# USST_ARM.net
KiCad netlist of a schematic drawn in Altium Designer
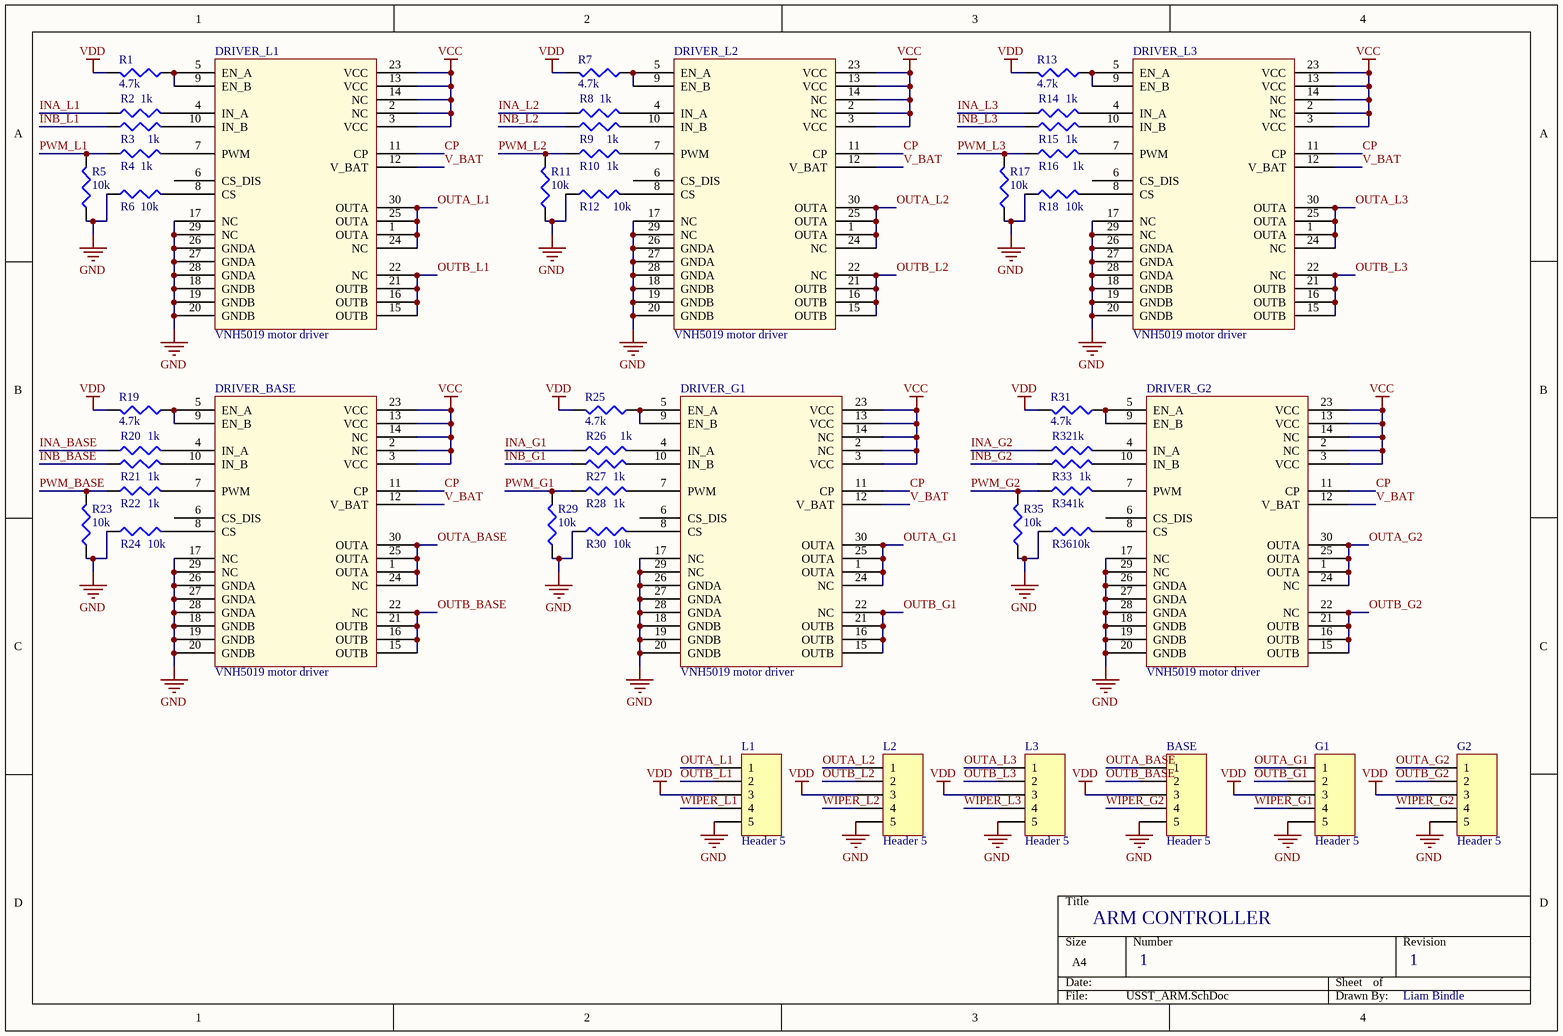
[diagram p0: USST_ARM.SchDoc]

(export (version "E")
  (design (tool "Eeschema 10.0.6"))
  (components
    (comp (ref "BASE")
      (value "Header 5")
      (footprint "HDR1X5")
      (description "Header, 5-Pin")
      (fields (field (name "PUBLISHER") "Altium Limited"))
      (libsource (lib "Miscellaneous Connectors") (part "Header 5"))
    )
    (comp (ref "DRIVER_BASE")
      (value "VNH5019 motor driver")
      (footprint "VNH5019_USST")
      (description "Motor driver")
      (libsource (lib "VNH5019_USST") (part "Component_1"))
    )
    (comp (ref "DRIVER_G1")
      (value "VNH5019 motor driver")
      (footprint "VNH5019_USST")
      (description "Motor driver")
      (libsource (lib "VNH5019_USST") (part "Component_1"))
    )
    (comp (ref "DRIVER_G2")
      (value "VNH5019 motor driver")
      (footprint "VNH5019_USST")
      (description "Motor driver")
      (libsource (lib "VNH5019_USST") (part "Component_1"))
    )
    (comp (ref "DRIVER_L1")
      (value "VNH5019 motor driver")
      (footprint "VNH5019_USST")
      (description "Motor driver")
      (libsource (lib "VNH5019_USST") (part "Component_1"))
    )
    (comp (ref "DRIVER_L2")
      (value "VNH5019 motor driver")
      (footprint "VNH5019_USST")
      (description "Motor driver")
      (libsource (lib "VNH5019_USST") (part "Component_1"))
    )
    (comp (ref "DRIVER_L3")
      (value "VNH5019 motor driver")
      (footprint "VNH5019_USST")
      (description "Motor driver")
      (libsource (lib "VNH5019_USST") (part "Component_1"))
    )
    (comp (ref "G1")
      (value "Header 5")
      (footprint "HDR1X5")
      (description "Header, 5-Pin")
      (fields (field (name "PUBLISHER") "Altium Limited"))
      (libsource (lib "Miscellaneous Connectors") (part "Header 5"))
    )
    (comp (ref "G2")
      (value "Header 5")
      (footprint "HDR1X5")
      (description "Header, 5-Pin")
      (fields (field (name "PUBLISHER") "Altium Limited"))
      (libsource (lib "Miscellaneous Connectors") (part "Header 5"))
    )
    (comp (ref "L1")
      (value "Header 5")
      (footprint "HDR1X5")
      (description "Header, 5-Pin")
      (fields (field (name "PUBLISHER") "Altium Limited"))
      (libsource (lib "Miscellaneous Connectors") (part "Header 5"))
    )
    (comp (ref "L2")
      (value "Header 5")
      (footprint "HDR1X5")
      (description "Header, 5-Pin")
      (fields (field (name "PUBLISHER") "Altium Limited"))
      (libsource (lib "Miscellaneous Connectors") (part "Header 5"))
    )
    (comp (ref "L3")
      (value "Header 5")
      (footprint "HDR1X5")
      (description "Header, 5-Pin")
      (fields (field (name "PUBLISHER") "Altium Limited"))
      (libsource (lib "Miscellaneous Connectors") (part "Header 5"))
    )
    (comp (ref "R1")
      (value "4.7k")
      (footprint "J1-0603")
      (description "Resistor")
      (fields (field (name "Comment") "Res3") (field (name "PUBLISHER") "Altium Limited"))
      (libsource (lib "Miscellaneous Devices") (part "Res3"))
    )
    (comp (ref "R2")
      (value "1k")
      (footprint "J1-0603")
      (description "Resistor")
      (fields (field (name "Comment") "Res3") (field (name "PUBLISHER") "Altium Limited"))
      (libsource (lib "Miscellaneous Devices") (part "Res3"))
    )
    (comp (ref "R3")
      (value "1k")
      (footprint "J1-0603")
      (description "Resistor")
      (fields (field (name "Comment") "Res3") (field (name "PUBLISHER") "Altium Limited"))
      (libsource (lib "Miscellaneous Devices") (part "Res3"))
    )
    (comp (ref "R4")
      (value "1k")
      (footprint "J1-0603")
      (description "Resistor")
      (fields (field (name "Comment") "Res3") (field (name "PUBLISHER") "Altium Limited"))
      (libsource (lib "Miscellaneous Devices") (part "Res3"))
    )
    (comp (ref "R5")
      (value "10k")
      (footprint "J1-0603")
      (description "Resistor")
      (fields (field (name "Comment") "Res3") (field (name "PUBLISHER") "Altium Limited"))
      (libsource (lib "Miscellaneous Devices") (part "Res3"))
    )
    (comp (ref "R6")
      (value "10k")
      (footprint "J1-0603")
      (description "Resistor")
      (fields (field (name "Comment") "Res3") (field (name "PUBLISHER") "Altium Limited"))
      (libsource (lib "Miscellaneous Devices") (part "Res3"))
    )
    (comp (ref "R7")
      (value "4.7k")
      (footprint "J1-0603")
      (description "Resistor")
      (fields (field (name "Comment") "Res3") (field (name "PUBLISHER") "Altium Limited"))
      (libsource (lib "Miscellaneous Devices") (part "Res3"))
    )
    (comp (ref "R8")
      (value "1k")
      (footprint "J1-0603")
      (description "Resistor")
      (fields (field (name "Comment") "Res3") (field (name "PUBLISHER") "Altium Limited"))
      (libsource (lib "Miscellaneous Devices") (part "Res3"))
    )
    (comp (ref "R9")
      (value "1k")
      (footprint "J1-0603")
      (description "Resistor")
      (fields (field (name "Comment") "Res3") (field (name "PUBLISHER") "Altium Limited"))
      (libsource (lib "Miscellaneous Devices") (part "Res3"))
    )
    (comp (ref "R10")
      (value "1k")
      (footprint "J1-0603")
      (description "Resistor")
      (fields (field (name "Comment") "Res3") (field (name "PUBLISHER") "Altium Limited"))
      (libsource (lib "Miscellaneous Devices") (part "Res3"))
    )
    (comp (ref "R11")
      (value "10k")
      (footprint "J1-0603")
      (description "Resistor")
      (fields (field (name "Comment") "Res3") (field (name "PUBLISHER") "Altium Limited"))
      (libsource (lib "Miscellaneous Devices") (part "Res3"))
    )
    (comp (ref "R12")
      (value "10k")
      (footprint "J1-0603")
      (description "Resistor")
      (fields (field (name "Comment") "Res3") (field (name "PUBLISHER") "Altium Limited"))
      (libsource (lib "Miscellaneous Devices") (part "Res3"))
    )
    (comp (ref "R13")
      (value "4.7k")
      (footprint "J1-0603")
      (description "Resistor")
      (fields (field (name "Comment") "Res3") (field (name "PUBLISHER") "Altium Limited"))
      (libsource (lib "Miscellaneous Devices") (part "Res3"))
    )
    (comp (ref "R14")
      (value "1k")
      (footprint "J1-0603")
      (description "Resistor")
      (fields (field (name "Comment") "Res3") (field (name "PUBLISHER") "Altium Limited"))
      (libsource (lib "Miscellaneous Devices") (part "Res3"))
    )
    (comp (ref "R15")
      (value "1k")
      (footprint "J1-0603")
      (description "Resistor")
      (fields (field (name "Comment") "Res3") (field (name "PUBLISHER") "Altium Limited"))
      (libsource (lib "Miscellaneous Devices") (part "Res3"))
    )
    (comp (ref "R16")
      (value "1k")
      (footprint "J1-0603")
      (description "Resistor")
      (fields (field (name "Comment") "Res3") (field (name "PUBLISHER") "Altium Limited"))
      (libsource (lib "Miscellaneous Devices") (part "Res3"))
    )
    (comp (ref "R17")
      (value "10k")
      (footprint "J1-0603")
      (description "Resistor")
      (fields (field (name "Comment") "Res3") (field (name "PUBLISHER") "Altium Limited"))
      (libsource (lib "Miscellaneous Devices") (part "Res3"))
    )
    (comp (ref "R18")
      (value "10k")
      (footprint "J1-0603")
      (description "Resistor")
      (fields (field (name "Comment") "Res3") (field (name "PUBLISHER") "Altium Limited"))
      (libsource (lib "Miscellaneous Devices") (part "Res3"))
    )
    (comp (ref "R19")
      (value "4.7k")
      (footprint "J1-0603")
      (description "Resistor")
      (fields (field (name "Comment") "Res3") (field (name "PUBLISHER") "Altium Limited"))
      (libsource (lib "Miscellaneous Devices") (part "Res3"))
    )
    (comp (ref "R20")
      (value "1k")
      (footprint "J1-0603")
      (description "Resistor")
      (fields (field (name "Comment") "Res3") (field (name "PUBLISHER") "Altium Limited"))
      (libsource (lib "Miscellaneous Devices") (part "Res3"))
    )
    (comp (ref "R21")
      (value "1k")
      (footprint "J1-0603")
      (description "Resistor")
      (fields (field (name "Comment") "Res3") (field (name "PUBLISHER") "Altium Limited"))
      (libsource (lib "Miscellaneous Devices") (part "Res3"))
    )
    (comp (ref "R22")
      (value "1k")
      (footprint "J1-0603")
      (description "Resistor")
      (fields (field (name "Comment") "Res3") (field (name "PUBLISHER") "Altium Limited"))
      (libsource (lib "Miscellaneous Devices") (part "Res3"))
    )
    (comp (ref "R23")
      (value "10k")
      (footprint "J1-0603")
      (description "Resistor")
      (fields (field (name "Comment") "Res3") (field (name "PUBLISHER") "Altium Limited"))
      (libsource (lib "Miscellaneous Devices") (part "Res3"))
    )
    (comp (ref "R24")
      (value "10k")
      (footprint "J1-0603")
      (description "Resistor")
      (fields (field (name "Comment") "Res3") (field (name "PUBLISHER") "Altium Limited"))
      (libsource (lib "Miscellaneous Devices") (part "Res3"))
    )
    (comp (ref "R25")
      (value "4.7k")
      (footprint "J1-0603")
      (description "Resistor")
      (fields (field (name "Comment") "Res3") (field (name "PUBLISHER") "Altium Limited"))
      (libsource (lib "Miscellaneous Devices") (part "Res3"))
    )
    (comp (ref "R26")
      (value "1k")
      (footprint "J1-0603")
      (description "Resistor")
      (fields (field (name "Comment") "Res3") (field (name "PUBLISHER") "Altium Limited"))
      (libsource (lib "Miscellaneous Devices") (part "Res3"))
    )
    (comp (ref "R27")
      (value "1k")
      (footprint "J1-0603")
      (description "Resistor")
      (fields (field (name "Comment") "Res3") (field (name "PUBLISHER") "Altium Limited"))
      (libsource (lib "Miscellaneous Devices") (part "Res3"))
    )
    (comp (ref "R28")
      (value "1k")
      (footprint "J1-0603")
      (description "Resistor")
      (fields (field (name "Comment") "Res3") (field (name "PUBLISHER") "Altium Limited"))
      (libsource (lib "Miscellaneous Devices") (part "Res3"))
    )
    (comp (ref "R29")
      (value "10k")
      (footprint "J1-0603")
      (description "Resistor")
      (fields (field (name "Comment") "Res3") (field (name "PUBLISHER") "Altium Limited"))
      (libsource (lib "Miscellaneous Devices") (part "Res3"))
    )
    (comp (ref "R30")
      (value "10k")
      (footprint "J1-0603")
      (description "Resistor")
      (fields (field (name "Comment") "Res3") (field (name "PUBLISHER") "Altium Limited"))
      (libsource (lib "Miscellaneous Devices") (part "Res3"))
    )
    (comp (ref "R31")
      (value "4.7k")
      (footprint "J1-0603")
      (description "Resistor")
      (fields (field (name "Comment") "Res3") (field (name "PUBLISHER") "Altium Limited"))
      (libsource (lib "Miscellaneous Devices") (part "Res3"))
    )
    (comp (ref "R32")
      (value "1k")
      (footprint "J1-0603")
      (description "Resistor")
      (fields (field (name "Comment") "Res3") (field (name "PUBLISHER") "Altium Limited"))
      (libsource (lib "Miscellaneous Devices") (part "Res3"))
    )
    (comp (ref "R33")
      (value "1k")
      (footprint "J1-0603")
      (description "Resistor")
      (fields (field (name "Comment") "Res3") (field (name "PUBLISHER") "Altium Limited"))
      (libsource (lib "Miscellaneous Devices") (part "Res3"))
    )
    (comp (ref "R34")
      (value "1k")
      (footprint "J1-0603")
      (description "Resistor")
      (fields (field (name "Comment") "Res3") (field (name "PUBLISHER") "Altium Limited"))
      (libsource (lib "Miscellaneous Devices") (part "Res3"))
    )
    (comp (ref "R35")
      (value "10k")
      (footprint "J1-0603")
      (description "Resistor")
      (fields (field (name "Comment") "Res3") (field (name "PUBLISHER") "Altium Limited"))
      (libsource (lib "Miscellaneous Devices") (part "Res3"))
    )
    (comp (ref "R36")
      (value "10k")
      (footprint "J1-0603")
      (description "Resistor")
      (fields (field (name "Comment") "Res3") (field (name "PUBLISHER") "Altium Limited"))
      (libsource (lib "Miscellaneous Devices") (part "Res3"))
    )
  )
  (nets
    (net (code "1") (name "/CP") (class "Default")
      (node (ref "DRIVER_BASE") (pin "11") (pinfunction "CP_11") (pintype "passive"))
      (node (ref "DRIVER_G1") (pin "11") (pinfunction "CP_11") (pintype "passive"))
      (node (ref "DRIVER_G2") (pin "11") (pinfunction "CP_11") (pintype "passive"))
      (node (ref "DRIVER_L1") (pin "11") (pinfunction "CP_11") (pintype "passive"))
      (node (ref "DRIVER_L2") (pin "11") (pinfunction "CP_11") (pintype "passive"))
      (node (ref "DRIVER_L3") (pin "11") (pinfunction "CP_11") (pintype "passive"))
    )
    (net (code "2") (name "/INA_BASE") (class "Default")
      (node (ref "R20") (pin "1") (pinfunction "1_1") (pintype "passive"))
    )
    (net (code "3") (name "/INA_G1") (class "Default")
      (node (ref "R26") (pin "1") (pinfunction "1_1") (pintype "passive"))
    )
    (net (code "4") (name "/INA_G2") (class "Default")
      (node (ref "R32") (pin "1") (pinfunction "1_1") (pintype "passive"))
    )
    (net (code "5") (name "/INA_L1") (class "Default")
      (node (ref "R2") (pin "1") (pinfunction "1_1") (pintype "passive"))
    )
    (net (code "6") (name "/INA_L2") (class "Default")
      (node (ref "R8") (pin "1") (pinfunction "1_1") (pintype "passive"))
    )
    (net (code "7") (name "/INA_L3") (class "Default")
      (node (ref "R14") (pin "1") (pinfunction "1_1") (pintype "passive"))
    )
    (net (code "8") (name "/INB_BASE") (class "Default")
      (node (ref "R21") (pin "1") (pinfunction "1_1") (pintype "passive"))
    )
    (net (code "9") (name "/INB_G1") (class "Default")
      (node (ref "R27") (pin "1") (pinfunction "1_1") (pintype "passive"))
    )
    (net (code "10") (name "/INB_G2") (class "Default")
      (node (ref "R33") (pin "1") (pinfunction "1_1") (pintype "passive"))
    )
    (net (code "11") (name "/INB_L1") (class "Default")
      (node (ref "R3") (pin "1") (pinfunction "1_1") (pintype "passive"))
    )
    (net (code "12") (name "/INB_L2") (class "Default")
      (node (ref "R9") (pin "1") (pinfunction "1_1") (pintype "passive"))
    )
    (net (code "13") (name "/INB_L3") (class "Default")
      (node (ref "R15") (pin "1") (pinfunction "1_1") (pintype "passive"))
    )
    (net (code "14") (name "/OUTA_BASE") (class "Default")
      (node (ref "BASE") (pin "1") (pinfunction "1_1") (pintype "passive"))
      (node (ref "DRIVER_BASE") (pin "1") (pinfunction "OUTA_1") (pintype "passive"))
      (node (ref "DRIVER_BASE") (pin "24") (pinfunction "NC_24") (pintype "passive"))
      (node (ref "DRIVER_BASE") (pin "25") (pinfunction "OUTA_25") (pintype "passive"))
      (node (ref "DRIVER_BASE") (pin "30") (pinfunction "OUTA_30") (pintype "passive"))
    )
    (net (code "15") (name "/OUTA_G1") (class "Default")
      (node (ref "DRIVER_G1") (pin "1") (pinfunction "OUTA_1") (pintype "passive"))
      (node (ref "DRIVER_G1") (pin "24") (pinfunction "NC_24") (pintype "passive"))
      (node (ref "DRIVER_G1") (pin "25") (pinfunction "OUTA_25") (pintype "passive"))
      (node (ref "DRIVER_G1") (pin "30") (pinfunction "OUTA_30") (pintype "passive"))
      (node (ref "G1") (pin "1") (pinfunction "1_1") (pintype "passive"))
    )
    (net (code "16") (name "/OUTA_G2") (class "Default")
      (node (ref "DRIVER_G2") (pin "1") (pinfunction "OUTA_1") (pintype "passive"))
      (node (ref "DRIVER_G2") (pin "24") (pinfunction "NC_24") (pintype "passive"))
      (node (ref "DRIVER_G2") (pin "25") (pinfunction "OUTA_25") (pintype "passive"))
      (node (ref "DRIVER_G2") (pin "30") (pinfunction "OUTA_30") (pintype "passive"))
      (node (ref "G2") (pin "1") (pinfunction "1_1") (pintype "passive"))
    )
    (net (code "17") (name "/OUTA_L1") (class "Default")
      (node (ref "DRIVER_L1") (pin "1") (pinfunction "OUTA_1") (pintype "passive"))
      (node (ref "DRIVER_L1") (pin "24") (pinfunction "NC_24") (pintype "passive"))
      (node (ref "DRIVER_L1") (pin "25") (pinfunction "OUTA_25") (pintype "passive"))
      (node (ref "DRIVER_L1") (pin "30") (pinfunction "OUTA_30") (pintype "passive"))
      (node (ref "L1") (pin "1") (pinfunction "1_1") (pintype "passive"))
    )
    (net (code "18") (name "/OUTA_L2") (class "Default")
      (node (ref "DRIVER_L2") (pin "1") (pinfunction "OUTA_1") (pintype "passive"))
      (node (ref "DRIVER_L2") (pin "24") (pinfunction "NC_24") (pintype "passive"))
      (node (ref "DRIVER_L2") (pin "25") (pinfunction "OUTA_25") (pintype "passive"))
      (node (ref "DRIVER_L2") (pin "30") (pinfunction "OUTA_30") (pintype "passive"))
      (node (ref "L2") (pin "1") (pinfunction "1_1") (pintype "passive"))
    )
    (net (code "19") (name "/OUTA_L3") (class "Default")
      (node (ref "DRIVER_L3") (pin "1") (pinfunction "OUTA_1") (pintype "passive"))
      (node (ref "DRIVER_L3") (pin "24") (pinfunction "NC_24") (pintype "passive"))
      (node (ref "DRIVER_L3") (pin "25") (pinfunction "OUTA_25") (pintype "passive"))
      (node (ref "DRIVER_L3") (pin "30") (pinfunction "OUTA_30") (pintype "passive"))
      (node (ref "L3") (pin "1") (pinfunction "1_1") (pintype "passive"))
    )
    (net (code "20") (name "/OUTB_BASE") (class "Default")
      (node (ref "BASE") (pin "2") (pinfunction "2_2") (pintype "passive"))
      (node (ref "DRIVER_BASE") (pin "15") (pinfunction "OUTB_15") (pintype "passive"))
      (node (ref "DRIVER_BASE") (pin "16") (pinfunction "OUTB_16") (pintype "passive"))
      (node (ref "DRIVER_BASE") (pin "21") (pinfunction "OUTB_21") (pintype "passive"))
      (node (ref "DRIVER_BASE") (pin "22") (pinfunction "NC_22") (pintype "passive"))
    )
    (net (code "21") (name "/OUTB_G1") (class "Default")
      (node (ref "DRIVER_G1") (pin "15") (pinfunction "OUTB_15") (pintype "passive"))
      (node (ref "DRIVER_G1") (pin "16") (pinfunction "OUTB_16") (pintype "passive"))
      (node (ref "DRIVER_G1") (pin "21") (pinfunction "OUTB_21") (pintype "passive"))
      (node (ref "DRIVER_G1") (pin "22") (pinfunction "NC_22") (pintype "passive"))
      (node (ref "G1") (pin "2") (pinfunction "2_2") (pintype "passive"))
    )
    (net (code "22") (name "/OUTB_G2") (class "Default")
      (node (ref "DRIVER_G2") (pin "15") (pinfunction "OUTB_15") (pintype "passive"))
      (node (ref "DRIVER_G2") (pin "16") (pinfunction "OUTB_16") (pintype "passive"))
      (node (ref "DRIVER_G2") (pin "21") (pinfunction "OUTB_21") (pintype "passive"))
      (node (ref "DRIVER_G2") (pin "22") (pinfunction "NC_22") (pintype "passive"))
      (node (ref "G2") (pin "2") (pinfunction "2_2") (pintype "passive"))
    )
    (net (code "23") (name "/OUTB_L1") (class "Default")
      (node (ref "DRIVER_L1") (pin "15") (pinfunction "OUTB_15") (pintype "passive"))
      (node (ref "DRIVER_L1") (pin "16") (pinfunction "OUTB_16") (pintype "passive"))
      (node (ref "DRIVER_L1") (pin "21") (pinfunction "OUTB_21") (pintype "passive"))
      (node (ref "DRIVER_L1") (pin "22") (pinfunction "NC_22") (pintype "passive"))
      (node (ref "L1") (pin "2") (pinfunction "2_2") (pintype "passive"))
    )
    (net (code "24") (name "/OUTB_L2") (class "Default")
      (node (ref "DRIVER_L2") (pin "15") (pinfunction "OUTB_15") (pintype "passive"))
      (node (ref "DRIVER_L2") (pin "16") (pinfunction "OUTB_16") (pintype "passive"))
      (node (ref "DRIVER_L2") (pin "21") (pinfunction "OUTB_21") (pintype "passive"))
      (node (ref "DRIVER_L2") (pin "22") (pinfunction "NC_22") (pintype "passive"))
      (node (ref "L2") (pin "2") (pinfunction "2_2") (pintype "passive"))
    )
    (net (code "25") (name "/OUTB_L3") (class "Default")
      (node (ref "DRIVER_L3") (pin "15") (pinfunction "OUTB_15") (pintype "passive"))
      (node (ref "DRIVER_L3") (pin "16") (pinfunction "OUTB_16") (pintype "passive"))
      (node (ref "DRIVER_L3") (pin "21") (pinfunction "OUTB_21") (pintype "passive"))
      (node (ref "DRIVER_L3") (pin "22") (pinfunction "NC_22") (pintype "passive"))
      (node (ref "L3") (pin "2") (pinfunction "2_2") (pintype "passive"))
    )
    (net (code "26") (name "/PWM_BASE") (class "Default")
      (node (ref "R22") (pin "1") (pinfunction "1_1") (pintype "passive"))
      (node (ref "R23") (pin "2") (pinfunction "2_2") (pintype "passive"))
    )
    (net (code "27") (name "/PWM_G1") (class "Default")
      (node (ref "R28") (pin "1") (pinfunction "1_1") (pintype "passive"))
      (node (ref "R29") (pin "2") (pinfunction "2_2") (pintype "passive"))
    )
    (net (code "28") (name "/PWM_G2") (class "Default")
      (node (ref "R34") (pin "1") (pinfunction "1_1") (pintype "passive"))
      (node (ref "R35") (pin "2") (pinfunction "2_2") (pintype "passive"))
    )
    (net (code "29") (name "/PWM_L1") (class "Default")
      (node (ref "R4") (pin "1") (pinfunction "1_1") (pintype "passive"))
      (node (ref "R5") (pin "2") (pinfunction "2_2") (pintype "passive"))
    )
    (net (code "30") (name "/PWM_L2") (class "Default")
      (node (ref "R10") (pin "1") (pinfunction "1_1") (pintype "passive"))
      (node (ref "R11") (pin "2") (pinfunction "2_2") (pintype "passive"))
    )
    (net (code "31") (name "/PWM_L3") (class "Default")
      (node (ref "R16") (pin "1") (pinfunction "1_1") (pintype "passive"))
      (node (ref "R17") (pin "2") (pinfunction "2_2") (pintype "passive"))
    )
    (net (code "32") (name "/V_BAT") (class "Default")
      (node (ref "DRIVER_BASE") (pin "12") (pinfunction "V_BAT_12") (pintype "passive"))
      (node (ref "DRIVER_G1") (pin "12") (pinfunction "V_BAT_12") (pintype "passive"))
      (node (ref "DRIVER_G2") (pin "12") (pinfunction "V_BAT_12") (pintype "passive"))
      (node (ref "DRIVER_L1") (pin "12") (pinfunction "V_BAT_12") (pintype "passive"))
      (node (ref "DRIVER_L2") (pin "12") (pinfunction "V_BAT_12") (pintype "passive"))
      (node (ref "DRIVER_L3") (pin "12") (pinfunction "V_BAT_12") (pintype "passive"))
    )
    (net (code "33") (name "/WIPER_G1") (class "Default")
      (node (ref "G1") (pin "4") (pinfunction "4_4") (pintype "passive"))
    )
    (net (code "34") (name "/WIPER_G2") (class "Default")
      (node (ref "BASE") (pin "4") (pinfunction "4_4") (pintype "passive"))
      (node (ref "G2") (pin "4") (pinfunction "4_4") (pintype "passive"))
    )
    (net (code "35") (name "/WIPER_L1") (class "Default")
      (node (ref "L1") (pin "4") (pinfunction "4_4") (pintype "passive"))
    )
    (net (code "36") (name "/WIPER_L2") (class "Default")
      (node (ref "L2") (pin "4") (pinfunction "4_4") (pintype "passive"))
    )
    (net (code "37") (name "/WIPER_L3") (class "Default")
      (node (ref "L3") (pin "4") (pinfunction "4_4") (pintype "passive"))
    )
    (net (code "38") (name "GND") (class "Default")
      (node (ref "BASE") (pin "5") (pinfunction "5_5") (pintype "passive"))
      (node (ref "DRIVER_BASE") (pin "17") (pinfunction "NC_17") (pintype "passive"))
      (node (ref "DRIVER_BASE") (pin "18") (pinfunction "GNDB_18") (pintype "passive"))
      (node (ref "DRIVER_BASE") (pin "19") (pinfunction "GNDB_19") (pintype "passive"))
      (node (ref "DRIVER_BASE") (pin "20") (pinfunction "GNDB_20") (pintype "passive"))
      (node (ref "DRIVER_BASE") (pin "26") (pinfunction "GNDA_26") (pintype "passive"))
      (node (ref "DRIVER_BASE") (pin "27") (pinfunction "GNDA_27") (pintype "passive"))
      (node (ref "DRIVER_BASE") (pin "28") (pinfunction "GNDA_28") (pintype "passive"))
      (node (ref "DRIVER_BASE") (pin "29") (pinfunction "NC_29") (pintype "passive"))
      (node (ref "DRIVER_G1") (pin "17") (pinfunction "NC_17") (pintype "passive"))
      (node (ref "DRIVER_G1") (pin "18") (pinfunction "GNDB_18") (pintype "passive"))
      (node (ref "DRIVER_G1") (pin "19") (pinfunction "GNDB_19") (pintype "passive"))
      (node (ref "DRIVER_G1") (pin "20") (pinfunction "GNDB_20") (pintype "passive"))
      (node (ref "DRIVER_G1") (pin "26") (pinfunction "GNDA_26") (pintype "passive"))
      (node (ref "DRIVER_G1") (pin "27") (pinfunction "GNDA_27") (pintype "passive"))
      (node (ref "DRIVER_G1") (pin "28") (pinfunction "GNDA_28") (pintype "passive"))
      (node (ref "DRIVER_G1") (pin "29") (pinfunction "NC_29") (pintype "passive"))
      (node (ref "DRIVER_G2") (pin "17") (pinfunction "NC_17") (pintype "passive"))
      (node (ref "DRIVER_G2") (pin "18") (pinfunction "GNDB_18") (pintype "passive"))
      (node (ref "DRIVER_G2") (pin "19") (pinfunction "GNDB_19") (pintype "passive"))
      (node (ref "DRIVER_G2") (pin "20") (pinfunction "GNDB_20") (pintype "passive"))
      (node (ref "DRIVER_G2") (pin "26") (pinfunction "GNDA_26") (pintype "passive"))
      (node (ref "DRIVER_G2") (pin "27") (pinfunction "GNDA_27") (pintype "passive"))
      (node (ref "DRIVER_G2") (pin "28") (pinfunction "GNDA_28") (pintype "passive"))
      (node (ref "DRIVER_G2") (pin "29") (pinfunction "NC_29") (pintype "passive"))
      (node (ref "DRIVER_L1") (pin "17") (pinfunction "NC_17") (pintype "passive"))
      (node (ref "DRIVER_L1") (pin "18") (pinfunction "GNDB_18") (pintype "passive"))
      (node (ref "DRIVER_L1") (pin "19") (pinfunction "GNDB_19") (pintype "passive"))
      (node (ref "DRIVER_L1") (pin "20") (pinfunction "GNDB_20") (pintype "passive"))
      (node (ref "DRIVER_L1") (pin "26") (pinfunction "GNDA_26") (pintype "passive"))
      (node (ref "DRIVER_L1") (pin "27") (pinfunction "GNDA_27") (pintype "passive"))
      (node (ref "DRIVER_L1") (pin "28") (pinfunction "GNDA_28") (pintype "passive"))
      (node (ref "DRIVER_L1") (pin "29") (pinfunction "NC_29") (pintype "passive"))
      (node (ref "DRIVER_L2") (pin "17") (pinfunction "NC_17") (pintype "passive"))
      (node (ref "DRIVER_L2") (pin "18") (pinfunction "GNDB_18") (pintype "passive"))
      (node (ref "DRIVER_L2") (pin "19") (pinfunction "GNDB_19") (pintype "passive"))
      (node (ref "DRIVER_L2") (pin "20") (pinfunction "GNDB_20") (pintype "passive"))
      (node (ref "DRIVER_L2") (pin "26") (pinfunction "GNDA_26") (pintype "passive"))
      (node (ref "DRIVER_L2") (pin "27") (pinfunction "GNDA_27") (pintype "passive"))
      (node (ref "DRIVER_L2") (pin "28") (pinfunction "GNDA_28") (pintype "passive"))
      (node (ref "DRIVER_L2") (pin "29") (pinfunction "NC_29") (pintype "passive"))
      (node (ref "DRIVER_L3") (pin "17") (pinfunction "NC_17") (pintype "passive"))
      (node (ref "DRIVER_L3") (pin "18") (pinfunction "GNDB_18") (pintype "passive"))
      (node (ref "DRIVER_L3") (pin "19") (pinfunction "GNDB_19") (pintype "passive"))
      (node (ref "DRIVER_L3") (pin "20") (pinfunction "GNDB_20") (pintype "passive"))
      (node (ref "DRIVER_L3") (pin "26") (pinfunction "GNDA_26") (pintype "passive"))
      (node (ref "DRIVER_L3") (pin "27") (pinfunction "GNDA_27") (pintype "passive"))
      (node (ref "DRIVER_L3") (pin "28") (pinfunction "GNDA_28") (pintype "passive"))
      (node (ref "DRIVER_L3") (pin "29") (pinfunction "NC_29") (pintype "passive"))
      (node (ref "G1") (pin "5") (pinfunction "5_5") (pintype "passive"))
      (node (ref "G2") (pin "5") (pinfunction "5_5") (pintype "passive"))
      (node (ref "L1") (pin "5") (pinfunction "5_5") (pintype "passive"))
      (node (ref "L2") (pin "5") (pinfunction "5_5") (pintype "passive"))
      (node (ref "L3") (pin "5") (pinfunction "5_5") (pintype "passive"))
      (node (ref "R11") (pin "1") (pinfunction "1_1") (pintype "passive"))
      (node (ref "R12") (pin "1") (pinfunction "1_1") (pintype "passive"))
      (node (ref "R17") (pin "1") (pinfunction "1_1") (pintype "passive"))
      (node (ref "R18") (pin "1") (pinfunction "1_1") (pintype "passive"))
      (node (ref "R23") (pin "1") (pinfunction "1_1") (pintype "passive"))
      (node (ref "R24") (pin "1") (pinfunction "1_1") (pintype "passive"))
      (node (ref "R29") (pin "1") (pinfunction "1_1") (pintype "passive"))
      (node (ref "R30") (pin "1") (pinfunction "1_1") (pintype "passive"))
      (node (ref "R35") (pin "1") (pinfunction "1_1") (pintype "passive"))
      (node (ref "R36") (pin "1") (pinfunction "1_1") (pintype "passive"))
      (node (ref "R5") (pin "1") (pinfunction "1_1") (pintype "passive"))
      (node (ref "R6") (pin "1") (pinfunction "1_1") (pintype "passive"))
    )
    (net (code "39") (name "Net-(DRIVER_BASE-CS)") (class "Default")
      (node (ref "DRIVER_BASE") (pin "8") (pinfunction "CS_8") (pintype "passive"))
      (node (ref "R24") (pin "2") (pinfunction "2_2") (pintype "passive"))
    )
    (net (code "40") (name "Net-(DRIVER_BASE-EN_A)") (class "Default")
      (node (ref "DRIVER_BASE") (pin "5") (pinfunction "EN_A_5") (pintype "passive"))
      (node (ref "DRIVER_BASE") (pin "9") (pinfunction "EN_B_9") (pintype "passive"))
      (node (ref "R19") (pin "1") (pinfunction "1_1") (pintype "passive"))
    )
    (net (code "41") (name "Net-(DRIVER_BASE-IN_A)") (class "Default")
      (node (ref "DRIVER_BASE") (pin "4") (pinfunction "IN_A_4") (pintype "passive"))
      (node (ref "R20") (pin "2") (pinfunction "2_2") (pintype "passive"))
    )
    (net (code "42") (name "Net-(DRIVER_BASE-IN_B)") (class "Default")
      (node (ref "DRIVER_BASE") (pin "10") (pinfunction "IN_B_10") (pintype "passive"))
      (node (ref "R21") (pin "2") (pinfunction "2_2") (pintype "passive"))
    )
    (net (code "43") (name "Net-(DRIVER_BASE-PWM)") (class "Default")
      (node (ref "DRIVER_BASE") (pin "7") (pinfunction "PWM_7") (pintype "passive"))
      (node (ref "R22") (pin "2") (pinfunction "2_2") (pintype "passive"))
    )
    (net (code "44") (name "Net-(DRIVER_G1-CS)") (class "Default")
      (node (ref "DRIVER_G1") (pin "8") (pinfunction "CS_8") (pintype "passive"))
      (node (ref "R30") (pin "2") (pinfunction "2_2") (pintype "passive"))
    )
    (net (code "45") (name "Net-(DRIVER_G1-EN_A)") (class "Default")
      (node (ref "DRIVER_G1") (pin "5") (pinfunction "EN_A_5") (pintype "passive"))
      (node (ref "DRIVER_G1") (pin "9") (pinfunction "EN_B_9") (pintype "passive"))
      (node (ref "R25") (pin "1") (pinfunction "1_1") (pintype "passive"))
    )
    (net (code "46") (name "Net-(DRIVER_G1-IN_A)") (class "Default")
      (node (ref "DRIVER_G1") (pin "4") (pinfunction "IN_A_4") (pintype "passive"))
      (node (ref "R26") (pin "2") (pinfunction "2_2") (pintype "passive"))
    )
    (net (code "47") (name "Net-(DRIVER_G1-IN_B)") (class "Default")
      (node (ref "DRIVER_G1") (pin "10") (pinfunction "IN_B_10") (pintype "passive"))
      (node (ref "R27") (pin "2") (pinfunction "2_2") (pintype "passive"))
    )
    (net (code "48") (name "Net-(DRIVER_G1-PWM)") (class "Default")
      (node (ref "DRIVER_G1") (pin "7") (pinfunction "PWM_7") (pintype "passive"))
      (node (ref "R28") (pin "2") (pinfunction "2_2") (pintype "passive"))
    )
    (net (code "49") (name "Net-(DRIVER_G2-CS)") (class "Default")
      (node (ref "DRIVER_G2") (pin "8") (pinfunction "CS_8") (pintype "passive"))
      (node (ref "R36") (pin "2") (pinfunction "2_2") (pintype "passive"))
    )
    (net (code "50") (name "Net-(DRIVER_G2-EN_A)") (class "Default")
      (node (ref "DRIVER_G2") (pin "5") (pinfunction "EN_A_5") (pintype "passive"))
      (node (ref "DRIVER_G2") (pin "9") (pinfunction "EN_B_9") (pintype "passive"))
      (node (ref "R31") (pin "1") (pinfunction "1_1") (pintype "passive"))
    )
    (net (code "51") (name "Net-(DRIVER_G2-IN_A)") (class "Default")
      (node (ref "DRIVER_G2") (pin "4") (pinfunction "IN_A_4") (pintype "passive"))
      (node (ref "R32") (pin "2") (pinfunction "2_2") (pintype "passive"))
    )
    (net (code "52") (name "Net-(DRIVER_G2-IN_B)") (class "Default")
      (node (ref "DRIVER_G2") (pin "10") (pinfunction "IN_B_10") (pintype "passive"))
      (node (ref "R33") (pin "2") (pinfunction "2_2") (pintype "passive"))
    )
    (net (code "53") (name "Net-(DRIVER_G2-PWM)") (class "Default")
      (node (ref "DRIVER_G2") (pin "7") (pinfunction "PWM_7") (pintype "passive"))
      (node (ref "R34") (pin "2") (pinfunction "2_2") (pintype "passive"))
    )
    (net (code "54") (name "Net-(DRIVER_L1-CS)") (class "Default")
      (node (ref "DRIVER_L1") (pin "8") (pinfunction "CS_8") (pintype "passive"))
      (node (ref "R6") (pin "2") (pinfunction "2_2") (pintype "passive"))
    )
    (net (code "55") (name "Net-(DRIVER_L1-EN_A)") (class "Default")
      (node (ref "DRIVER_L1") (pin "5") (pinfunction "EN_A_5") (pintype "passive"))
      (node (ref "DRIVER_L1") (pin "9") (pinfunction "EN_B_9") (pintype "passive"))
      (node (ref "R1") (pin "1") (pinfunction "1_1") (pintype "passive"))
    )
    (net (code "56") (name "Net-(DRIVER_L1-IN_A)") (class "Default")
      (node (ref "DRIVER_L1") (pin "4") (pinfunction "IN_A_4") (pintype "passive"))
      (node (ref "R2") (pin "2") (pinfunction "2_2") (pintype "passive"))
    )
    (net (code "57") (name "Net-(DRIVER_L1-IN_B)") (class "Default")
      (node (ref "DRIVER_L1") (pin "10") (pinfunction "IN_B_10") (pintype "passive"))
      (node (ref "R3") (pin "2") (pinfunction "2_2") (pintype "passive"))
    )
    (net (code "58") (name "Net-(DRIVER_L1-PWM)") (class "Default")
      (node (ref "DRIVER_L1") (pin "7") (pinfunction "PWM_7") (pintype "passive"))
      (node (ref "R4") (pin "2") (pinfunction "2_2") (pintype "passive"))
    )
    (net (code "59") (name "Net-(DRIVER_L2-CS)") (class "Default")
      (node (ref "DRIVER_L2") (pin "8") (pinfunction "CS_8") (pintype "passive"))
      (node (ref "R12") (pin "2") (pinfunction "2_2") (pintype "passive"))
    )
    (net (code "60") (name "Net-(DRIVER_L2-EN_A)") (class "Default")
      (node (ref "DRIVER_L2") (pin "5") (pinfunction "EN_A_5") (pintype "passive"))
      (node (ref "DRIVER_L2") (pin "9") (pinfunction "EN_B_9") (pintype "passive"))
      (node (ref "R7") (pin "1") (pinfunction "1_1") (pintype "passive"))
    )
    (net (code "61") (name "Net-(DRIVER_L2-IN_A)") (class "Default")
      (node (ref "DRIVER_L2") (pin "4") (pinfunction "IN_A_4") (pintype "passive"))
      (node (ref "R8") (pin "2") (pinfunction "2_2") (pintype "passive"))
    )
    (net (code "62") (name "Net-(DRIVER_L2-IN_B)") (class "Default")
      (node (ref "DRIVER_L2") (pin "10") (pinfunction "IN_B_10") (pintype "passive"))
      (node (ref "R9") (pin "2") (pinfunction "2_2") (pintype "passive"))
    )
    (net (code "63") (name "Net-(DRIVER_L2-PWM)") (class "Default")
      (node (ref "DRIVER_L2") (pin "7") (pinfunction "PWM_7") (pintype "passive"))
      (node (ref "R10") (pin "2") (pinfunction "2_2") (pintype "passive"))
    )
    (net (code "64") (name "Net-(DRIVER_L3-CS)") (class "Default")
      (node (ref "DRIVER_L3") (pin "8") (pinfunction "CS_8") (pintype "passive"))
      (node (ref "R18") (pin "2") (pinfunction "2_2") (pintype "passive"))
    )
    (net (code "65") (name "Net-(DRIVER_L3-EN_A)") (class "Default")
      (node (ref "DRIVER_L3") (pin "5") (pinfunction "EN_A_5") (pintype "passive"))
      (node (ref "DRIVER_L3") (pin "9") (pinfunction "EN_B_9") (pintype "passive"))
      (node (ref "R13") (pin "1") (pinfunction "1_1") (pintype "passive"))
    )
    (net (code "66") (name "Net-(DRIVER_L3-IN_A)") (class "Default")
      (node (ref "DRIVER_L3") (pin "4") (pinfunction "IN_A_4") (pintype "passive"))
      (node (ref "R14") (pin "2") (pinfunction "2_2") (pintype "passive"))
    )
    (net (code "67") (name "Net-(DRIVER_L3-IN_B)") (class "Default")
      (node (ref "DRIVER_L3") (pin "10") (pinfunction "IN_B_10") (pintype "passive"))
      (node (ref "R15") (pin "2") (pinfunction "2_2") (pintype "passive"))
    )
    (net (code "68") (name "Net-(DRIVER_L3-PWM)") (class "Default")
      (node (ref "DRIVER_L3") (pin "7") (pinfunction "PWM_7") (pintype "passive"))
      (node (ref "R16") (pin "2") (pinfunction "2_2") (pintype "passive"))
    )
    (net (code "69") (name "VCC") (class "Default")
      (node (ref "DRIVER_BASE") (pin "13") (pinfunction "VCC_13") (pintype "passive"))
      (node (ref "DRIVER_BASE") (pin "14") (pinfunction "NC_14") (pintype "passive"))
      (node (ref "DRIVER_BASE") (pin "2") (pinfunction "NC_2") (pintype "passive"))
      (node (ref "DRIVER_BASE") (pin "23") (pinfunction "VCC_23") (pintype "passive"))
      (node (ref "DRIVER_BASE") (pin "3") (pinfunction "VCC_3") (pintype "passive"))
      (node (ref "DRIVER_G1") (pin "13") (pinfunction "VCC_13") (pintype "passive"))
      (node (ref "DRIVER_G1") (pin "14") (pinfunction "NC_14") (pintype "passive"))
      (node (ref "DRIVER_G1") (pin "2") (pinfunction "NC_2") (pintype "passive"))
      (node (ref "DRIVER_G1") (pin "23") (pinfunction "VCC_23") (pintype "passive"))
      (node (ref "DRIVER_G1") (pin "3") (pinfunction "VCC_3") (pintype "passive"))
      (node (ref "DRIVER_G2") (pin "13") (pinfunction "VCC_13") (pintype "passive"))
      (node (ref "DRIVER_G2") (pin "14") (pinfunction "NC_14") (pintype "passive"))
      (node (ref "DRIVER_G2") (pin "2") (pinfunction "NC_2") (pintype "passive"))
      (node (ref "DRIVER_G2") (pin "23") (pinfunction "VCC_23") (pintype "passive"))
      (node (ref "DRIVER_G2") (pin "3") (pinfunction "VCC_3") (pintype "passive"))
      (node (ref "DRIVER_L1") (pin "13") (pinfunction "VCC_13") (pintype "passive"))
      (node (ref "DRIVER_L1") (pin "14") (pinfunction "NC_14") (pintype "passive"))
      (node (ref "DRIVER_L1") (pin "2") (pinfunction "NC_2") (pintype "passive"))
      (node (ref "DRIVER_L1") (pin "23") (pinfunction "VCC_23") (pintype "passive"))
      (node (ref "DRIVER_L1") (pin "3") (pinfunction "VCC_3") (pintype "passive"))
      (node (ref "DRIVER_L2") (pin "13") (pinfunction "VCC_13") (pintype "passive"))
      (node (ref "DRIVER_L2") (pin "14") (pinfunction "NC_14") (pintype "passive"))
      (node (ref "DRIVER_L2") (pin "2") (pinfunction "NC_2") (pintype "passive"))
      (node (ref "DRIVER_L2") (pin "23") (pinfunction "VCC_23") (pintype "passive"))
      (node (ref "DRIVER_L2") (pin "3") (pinfunction "VCC_3") (pintype "passive"))
      (node (ref "DRIVER_L3") (pin "13") (pinfunction "VCC_13") (pintype "passive"))
      (node (ref "DRIVER_L3") (pin "14") (pinfunction "NC_14") (pintype "passive"))
      (node (ref "DRIVER_L3") (pin "2") (pinfunction "NC_2") (pintype "passive"))
      (node (ref "DRIVER_L3") (pin "23") (pinfunction "VCC_23") (pintype "passive"))
      (node (ref "DRIVER_L3") (pin "3") (pinfunction "VCC_3") (pintype "passive"))
    )
    (net (code "70") (name "VDD") (class "Default")
      (node (ref "BASE") (pin "3") (pinfunction "3_3") (pintype "passive"))
      (node (ref "G1") (pin "3") (pinfunction "3_3") (pintype "passive"))
      (node (ref "G2") (pin "3") (pinfunction "3_3") (pintype "passive"))
      (node (ref "L1") (pin "3") (pinfunction "3_3") (pintype "passive"))
      (node (ref "L2") (pin "3") (pinfunction "3_3") (pintype "passive"))
      (node (ref "L3") (pin "3") (pinfunction "3_3") (pintype "passive"))
      (node (ref "R1") (pin "2") (pinfunction "2_2") (pintype "passive"))
      (node (ref "R13") (pin "2") (pinfunction "2_2") (pintype "passive"))
      (node (ref "R19") (pin "2") (pinfunction "2_2") (pintype "passive"))
      (node (ref "R25") (pin "2") (pinfunction "2_2") (pintype "passive"))
      (node (ref "R31") (pin "2") (pinfunction "2_2") (pintype "passive"))
      (node (ref "R7") (pin "2") (pinfunction "2_2") (pintype "passive"))
    )
    (net (code "71") (name "unconnected-(DRIVER_BASE-CS_DIS-Pad6)") (class "Default")
      (node (ref "DRIVER_BASE") (pin "6") (pinfunction "CS_DIS_6") (pintype "passive"))
    )
    (net (code "72") (name "unconnected-(DRIVER_G1-CS_DIS-Pad6)") (class "Default")
      (node (ref "DRIVER_G1") (pin "6") (pinfunction "CS_DIS_6") (pintype "passive"))
    )
    (net (code "73") (name "unconnected-(DRIVER_G2-CS_DIS-Pad6)") (class "Default")
      (node (ref "DRIVER_G2") (pin "6") (pinfunction "CS_DIS_6") (pintype "passive"))
    )
    (net (code "74") (name "unconnected-(DRIVER_L1-CS_DIS-Pad6)") (class "Default")
      (node (ref "DRIVER_L1") (pin "6") (pinfunction "CS_DIS_6") (pintype "passive"))
    )
    (net (code "75") (name "unconnected-(DRIVER_L2-CS_DIS-Pad6)") (class "Default")
      (node (ref "DRIVER_L2") (pin "6") (pinfunction "CS_DIS_6") (pintype "passive"))
    )
    (net (code "76") (name "unconnected-(DRIVER_L3-CS_DIS-Pad6)") (class "Default")
      (node (ref "DRIVER_L3") (pin "6") (pinfunction "CS_DIS_6") (pintype "passive"))
    )
  )
)
